# EDCPSU.net
KiCad netlist of a schematic drawn in EAGLE
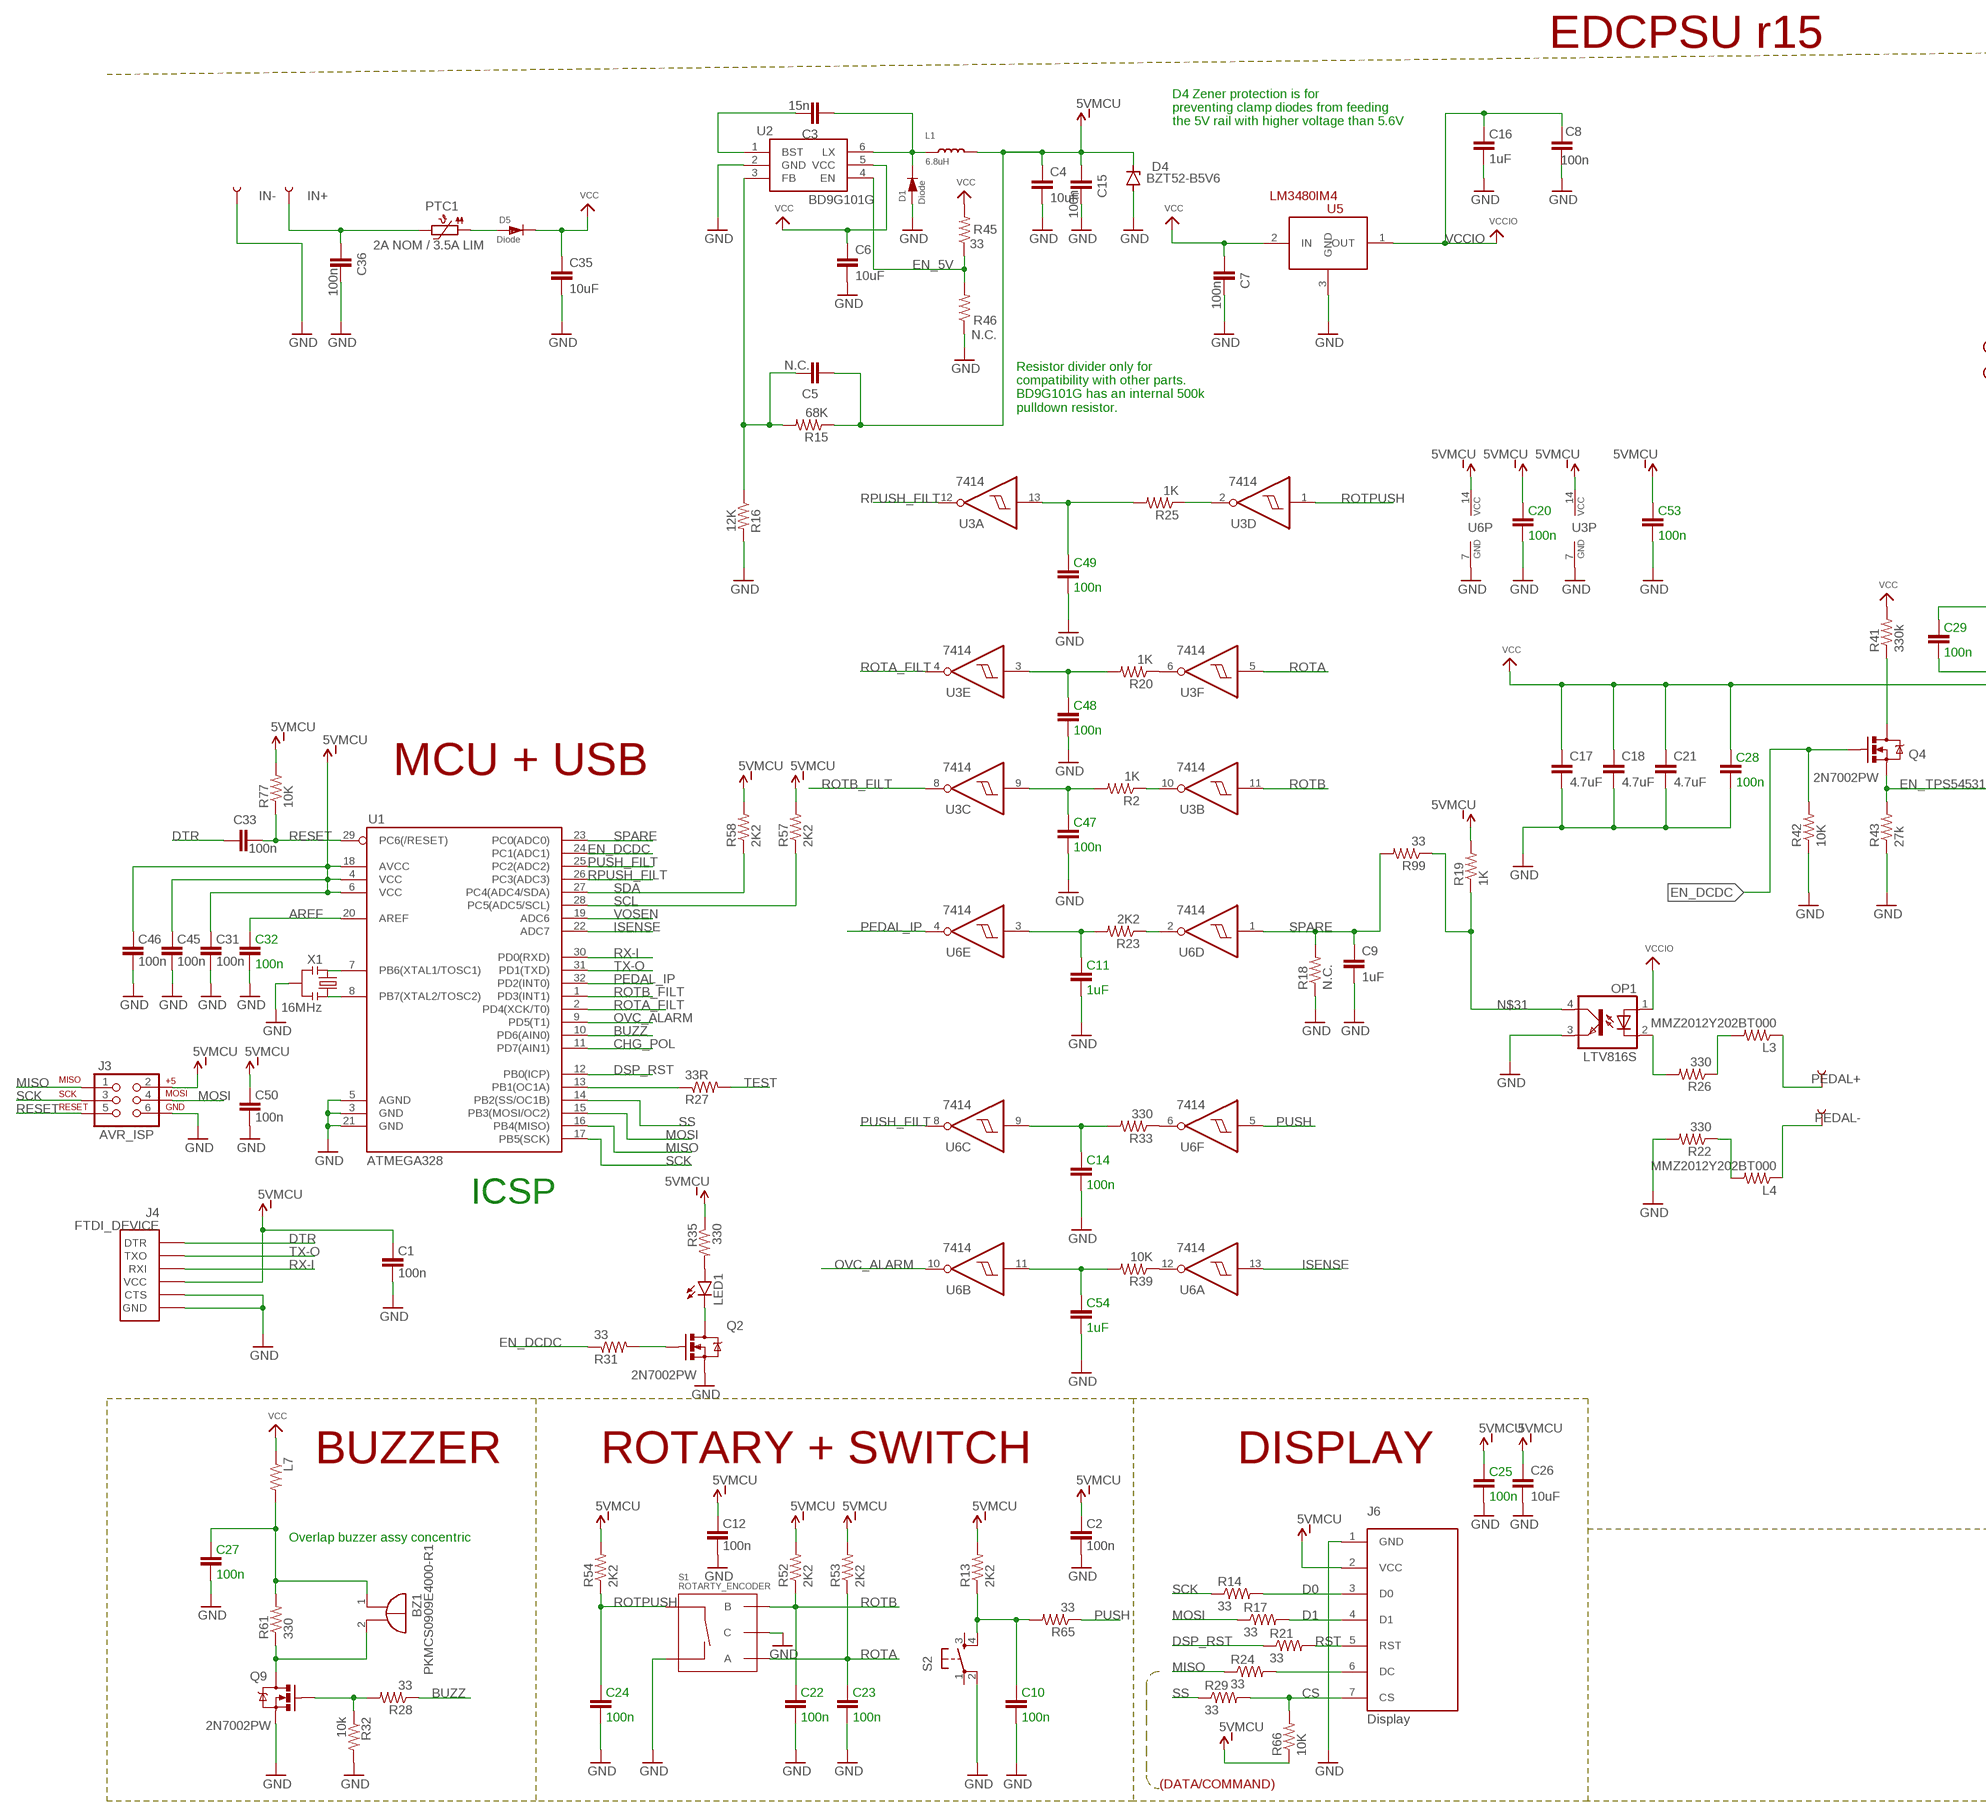
[diagram p0: schematic, sheet 1, part 1 of 2]
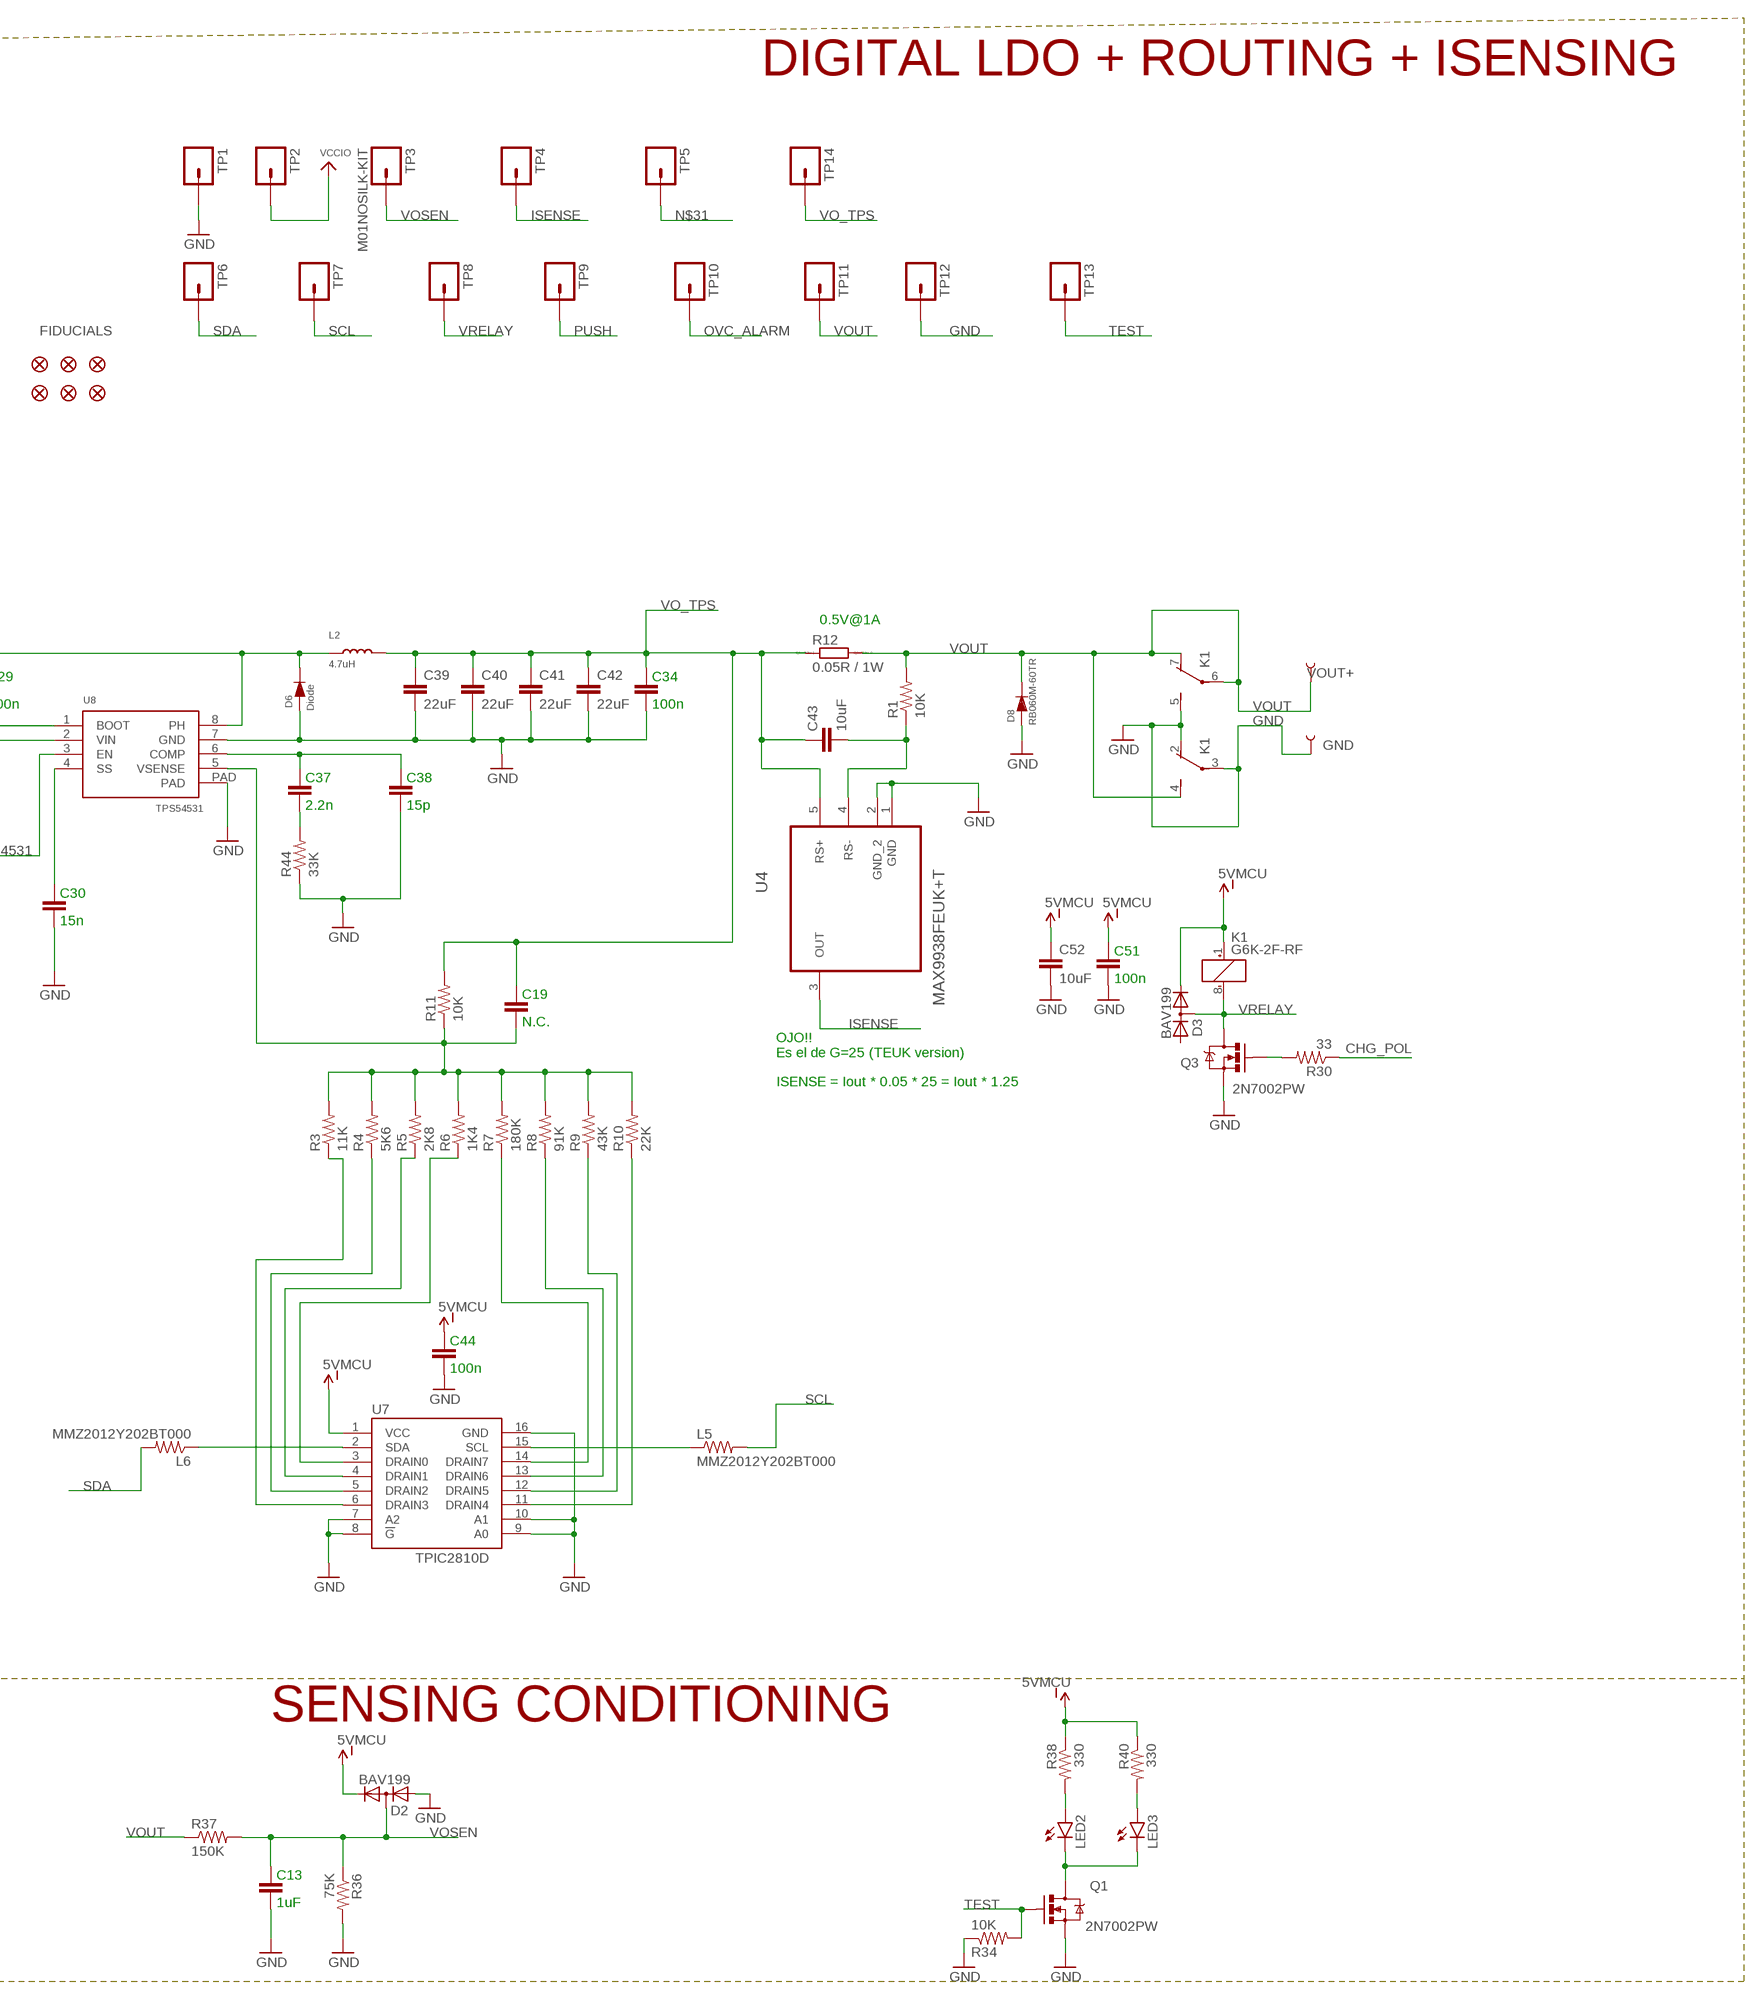
[diagram p1: schematic, sheet 1, part 2 of 2]

(export (version "E")
  (design (tool "Eeschema 10.0.6"))
  (components
    (comp (ref "BZ1")
      (value "PKMCS0909E4000-R1")
      (footprint "eagle-import:PKMCS0909")
      (libsource (lib "eagle-import") (part "PKMCS0909E4000-R1"))
    )
    (comp (ref "C1")
      (value "100n")
      (footprint "eagle-import:0805")
      (libsource (lib "eagle-import") (part "CAP0805"))
    )
    (comp (ref "C2")
      (value "100n")
      (footprint "eagle-import:0805")
      (libsource (lib "eagle-import") (part "CAP0805"))
    )
    (comp (ref "C3")
      (value "15n")
      (footprint "eagle-import:0805")
      (libsource (lib "eagle-import") (part "CAP0805"))
    )
    (comp (ref "C4")
      (value "10uF")
      (footprint "eagle-import:1206")
      (libsource (lib "eagle-import") (part "SparkFun-Passives_CAP1206"))
    )
    (comp (ref "C5")
      (value "N.C.")
      (footprint "eagle-import:0805")
      (libsource (lib "eagle-import") (part "CAP0805"))
    )
    (comp (ref "C6")
      (value "10uF")
      (footprint "eagle-import:1206")
      (libsource (lib "eagle-import") (part "SparkFun-Passives_CAP1206"))
    )
    (comp (ref "C7")
      (value "100n")
      (footprint "eagle-import:0805")
      (libsource (lib "eagle-import") (part "CAP0805"))
    )
    (comp (ref "C8")
      (value "100n")
      (footprint "eagle-import:0805")
      (libsource (lib "eagle-import") (part "CAP0805"))
    )
    (comp (ref "C9")
      (value "1uF")
      (footprint "eagle-import:1206")
      (libsource (lib "eagle-import") (part "SparkFun-Passives_CAP1206"))
    )
    (comp (ref "C10")
      (value "100n")
      (footprint "eagle-import:0805")
      (libsource (lib "eagle-import") (part "CAP0805"))
    )
    (comp (ref "C11")
      (value "1uF")
      (footprint "eagle-import:0805")
      (libsource (lib "eagle-import") (part "CAP0805"))
    )
    (comp (ref "C12")
      (value "100n")
      (footprint "eagle-import:0805")
      (libsource (lib "eagle-import") (part "CAP0805"))
    )
    (comp (ref "C13")
      (value "1uF")
      (footprint "eagle-import:0805")
      (libsource (lib "eagle-import") (part "CAP0805"))
    )
    (comp (ref "C14")
      (value "100n")
      (footprint "eagle-import:0805")
      (libsource (lib "eagle-import") (part "CAP0805"))
    )
    (comp (ref "C15")
      (value "100n")
      (footprint "eagle-import:0805")
      (libsource (lib "eagle-import") (part "CAP0805"))
    )
    (comp (ref "C16")
      (value "1uF")
      (footprint "eagle-import:0805")
      (libsource (lib "eagle-import") (part "CAP0805"))
    )
    (comp (ref "C17")
      (value "4.7uF")
      (footprint "eagle-import:1210")
      (libsource (lib "eagle-import") (part "SparkFun-Passives_CAP1210"))
    )
    (comp (ref "C18")
      (value "4.7uF")
      (footprint "eagle-import:1210")
      (libsource (lib "eagle-import") (part "SparkFun-Passives_CAP1210"))
    )
    (comp (ref "C19")
      (value "N.C.")
      (footprint "eagle-import:0805")
      (libsource (lib "eagle-import") (part "CAP0805"))
    )
    (comp (ref "C20")
      (value "100n")
      (footprint "eagle-import:0805")
      (libsource (lib "eagle-import") (part "CAP0805"))
    )
    (comp (ref "C21")
      (value "4.7uF")
      (footprint "eagle-import:1210")
      (libsource (lib "eagle-import") (part "SparkFun-Passives_CAP1210"))
    )
    (comp (ref "C22")
      (value "100n")
      (footprint "eagle-import:0805")
      (libsource (lib "eagle-import") (part "CAP0805"))
    )
    (comp (ref "C23")
      (value "100n")
      (footprint "eagle-import:0805")
      (libsource (lib "eagle-import") (part "CAP0805"))
    )
    (comp (ref "C24")
      (value "100n")
      (footprint "eagle-import:0805")
      (libsource (lib "eagle-import") (part "CAP0805"))
    )
    (comp (ref "C25")
      (value "100n")
      (footprint "eagle-import:0805")
      (libsource (lib "eagle-import") (part "CAP0805"))
    )
    (comp (ref "C26")
      (value "10uF")
      (footprint "eagle-import:1206")
      (libsource (lib "eagle-import") (part "SparkFun-Passives_CAP1206"))
    )
    (comp (ref "C27")
      (value "100n")
      (footprint "eagle-import:0805")
      (libsource (lib "eagle-import") (part "CAP0805"))
    )
    (comp (ref "C28")
      (value "100n")
      (footprint "eagle-import:0805")
      (libsource (lib "eagle-import") (part "CAP0805"))
    )
    (comp (ref "C29")
      (value "100n")
      (footprint "eagle-import:0805")
      (libsource (lib "eagle-import") (part "CAP0805"))
    )
    (comp (ref "C30")
      (value "15n")
      (footprint "eagle-import:0805")
      (libsource (lib "eagle-import") (part "CAP0805"))
    )
    (comp (ref "C31")
      (value "100n")
      (footprint "eagle-import:0805")
      (libsource (lib "eagle-import") (part "CAP0805"))
    )
    (comp (ref "C32")
      (value "100n")
      (footprint "eagle-import:0805")
      (libsource (lib "eagle-import") (part "CAP0805"))
    )
    (comp (ref "C33")
      (value "100n")
      (footprint "eagle-import:0805")
      (libsource (lib "eagle-import") (part "CAP0805"))
    )
    (comp (ref "C34")
      (value "100n")
      (footprint "eagle-import:0805")
      (libsource (lib "eagle-import") (part "CAP0805"))
    )
    (comp (ref "C35")
      (value "10uF")
      (footprint "eagle-import:1206")
      (libsource (lib "eagle-import") (part "SparkFun-Passives_CAP1206"))
    )
    (comp (ref "C36")
      (value "100n")
      (footprint "eagle-import:0805")
      (libsource (lib "eagle-import") (part "CAP0805"))
    )
    (comp (ref "C37")
      (value "2.2n")
      (footprint "eagle-import:0805")
      (libsource (lib "eagle-import") (part "CAP0805"))
    )
    (comp (ref "C38")
      (value "15p")
      (footprint "eagle-import:0805")
      (libsource (lib "eagle-import") (part "CAP0805"))
    )
    (comp (ref "C39")
      (value "22uF")
      (footprint "eagle-import:1210")
      (libsource (lib "eagle-import") (part "SparkFun-Passives_CAP1210"))
    )
    (comp (ref "C40")
      (value "22uF")
      (footprint "eagle-import:1210")
      (libsource (lib "eagle-import") (part "SparkFun-Passives_CAP1210"))
    )
    (comp (ref "C41")
      (value "22uF")
      (footprint "eagle-import:1210")
      (libsource (lib "eagle-import") (part "SparkFun-Passives_CAP1210"))
    )
    (comp (ref "C42")
      (value "22uF")
      (footprint "eagle-import:1210")
      (libsource (lib "eagle-import") (part "SparkFun-Passives_CAP1210"))
    )
    (comp (ref "C43")
      (value "10uF")
      (footprint "eagle-import:1206")
      (libsource (lib "eagle-import") (part "SparkFun-Passives_CAP1206"))
    )
    (comp (ref "C44")
      (value "100n")
      (footprint "eagle-import:0805")
      (libsource (lib "eagle-import") (part "CAP0805"))
    )
    (comp (ref "C45")
      (value "100n")
      (footprint "eagle-import:0805")
      (libsource (lib "eagle-import") (part "CAP0805"))
    )
    (comp (ref "C46")
      (value "100n")
      (footprint "eagle-import:0805")
      (libsource (lib "eagle-import") (part "CAP0805"))
    )
    (comp (ref "C47")
      (value "100n")
      (footprint "eagle-import:0805")
      (libsource (lib "eagle-import") (part "CAP0805"))
    )
    (comp (ref "C48")
      (value "100n")
      (footprint "eagle-import:0805")
      (libsource (lib "eagle-import") (part "CAP0805"))
    )
    (comp (ref "C49")
      (value "100n")
      (footprint "eagle-import:0805")
      (libsource (lib "eagle-import") (part "CAP0805"))
    )
    (comp (ref "C50")
      (value "100n")
      (footprint "eagle-import:0805")
      (libsource (lib "eagle-import") (part "CAP0805"))
    )
    (comp (ref "C51")
      (value "100n")
      (footprint "eagle-import:0805")
      (libsource (lib "eagle-import") (part "CAP0805"))
    )
    (comp (ref "C52")
      (value "10uF")
      (footprint "eagle-import:1206")
      (libsource (lib "eagle-import") (part "SparkFun-Passives_CAP1206"))
    )
    (comp (ref "C53")
      (value "100n")
      (footprint "eagle-import:0805")
      (libsource (lib "eagle-import") (part "CAP0805"))
    )
    (comp (ref "C54")
      (value "1uF")
      (footprint "eagle-import:0805")
      (libsource (lib "eagle-import") (part "CAP0805"))
    )
    (comp (ref "D1")
      (value "Diode")
      (footprint "eagle-import:SOD123")
      (libsource (lib "eagle-import") (part "DSOD123"))
    )
    (comp (ref "D2")
      (value "BAV199")
      (footprint "eagle-import:SOT23")
      (libsource (lib "eagle-import") (part "BAV199"))
    )
    (comp (ref "D3")
      (value "BAV199")
      (footprint "eagle-import:SOT23")
      (libsource (lib "eagle-import") (part "BAV199"))
    )
    (comp (ref "D4")
      (value "BZT52-B5V6")
      (footprint "eagle-import:SODFL3718X115")
      (libsource (lib "eagle-import") (part "ZENERDO-219-AB(SOD123F)_"))
    )
    (comp (ref "D5")
      (value "Diode")
      (footprint "eagle-import:DO-214AB")
      (libsource (lib "eagle-import") (part "DSMC"))
    )
    (comp (ref "D6")
      (value "Diode")
      (footprint "eagle-import:DO-214AB")
      (libsource (lib "eagle-import") (part "DSMC"))
    )
    (comp (ref "D8")
      (value "RB060M-60TR")
      (footprint "eagle-import:SMADIODE")
      (libsource (lib "eagle-import") (part "DSMA"))
    )
    (comp (ref "FID1")
      (value "FIDUCIAL1X2")
      (footprint "eagle-import:FIDUCIAL-1X2")
      (libsource (lib "eagle-import") (part "FIDUCIAL1X2"))
    )
    (comp (ref "FID2")
      (value "FIDUCIAL1X2")
      (footprint "eagle-import:FIDUCIAL-1X2")
      (libsource (lib "eagle-import") (part "FIDUCIAL1X2"))
    )
    (comp (ref "FID3")
      (value "FIDUCIAL1X2")
      (footprint "eagle-import:FIDUCIAL-1X2")
      (libsource (lib "eagle-import") (part "FIDUCIAL1X2"))
    )
    (comp (ref "FID4")
      (value "FIDUCIAL1X2")
      (footprint "eagle-import:FIDUCIAL-1X2")
      (libsource (lib "eagle-import") (part "FIDUCIAL1X2"))
    )
    (comp (ref "FID5")
      (value "FIDUCIAL1X2")
      (footprint "eagle-import:FIDUCIAL-1X2")
      (libsource (lib "eagle-import") (part "FIDUCIAL1X2"))
    )
    (comp (ref "FID6")
      (value "FIDUCIAL1X2")
      (footprint "eagle-import:FIDUCIAL-1X2")
      (libsource (lib "eagle-import") (part "FIDUCIAL1X2"))
    )
    (comp (ref "GND")
      (value "TEST-POINT3")
      (footprint "eagle-import:PAD.03X.03")
      (libsource (lib "eagle-import") (part "TEST-POINT3"))
    )
    (comp (ref "IN+")
      (value "TEST-POINT3")
      (footprint "eagle-import:PAD.03X.03")
      (libsource (lib "eagle-import") (part "TEST-POINT3"))
    )
    (comp (ref "IN-")
      (value "TEST-POINT3")
      (footprint "eagle-import:PAD.03X.03")
      (libsource (lib "eagle-import") (part "TEST-POINT3"))
    )
    (comp (ref "J3")
      (value "AVR_ISP")
      (footprint "eagle-import:2X3")
      (libsource (lib "eagle-import") (part "AVR_SPI_PRG_6PTH"))
    )
    (comp (ref "J4")
      (value "FTDI_DEVICE")
      (footprint "eagle-import:FTDI_DEVICE_SIDE")
      (libsource (lib "eagle-import") (part "FTDI_DEVICE"))
    )
    (comp (ref "J6")
      (value "Display")
      (footprint "eagle-import:OLED_LCD")
      (libsource (lib "eagle-import") (part "OLED_LCD"))
    )
    (comp (ref "K1")
      (value "G6K-2F-RF")
      (footprint "eagle-import:G6K-RF")
      (fields (field (name "MF") "OMRON COMPONENTS USA") (field (name "MPN") "G6K-2F-RF-DC12"))
      (libsource (lib "eagle-import") (part "G6K-2F-RF"))
    )
    (comp (ref "L1")
      (value "6.8uH")
      (footprint "eagle-import:NR4018T100M")
      (libsource (lib "eagle-import") (part "L4018"))
    )
    (comp (ref "L2")
      (value "4.7uH")
      (footprint "eagle-import:WE-LHMI")
      (libsource (lib "eagle-import") (part "L74437368047"))
    )
    (comp (ref "L3")
      (value "MMZ2012Y202BT000")
      (footprint "eagle-import:0805")
      (libsource (lib "eagle-import") (part "RESISTOR0805-RES"))
    )
    (comp (ref "L4")
      (value "MMZ2012Y202BT000")
      (footprint "eagle-import:0805")
      (libsource (lib "eagle-import") (part "RESISTOR0805-RES"))
    )
    (comp (ref "L5")
      (value "MMZ2012Y202BT000")
      (footprint "eagle-import:0805")
      (libsource (lib "eagle-import") (part "RESISTOR0805-RES"))
    )
    (comp (ref "L6")
      (value "MMZ2012Y202BT000")
      (footprint "eagle-import:0805")
      (libsource (lib "eagle-import") (part "RESISTOR0805-RES"))
    )
    (comp (ref "L7")
      (value "MMZ2012Y202BT000")
      (footprint "eagle-import:0805")
      (libsource (lib "eagle-import") (part "RESISTOR0805-RES"))
    )
    (comp (ref "LED1")
      (value "LED3MM")
      (footprint "eagle-import:LED3MM")
      (libsource (lib "eagle-import") (part "LED3MM"))
    )
    (comp (ref "LED2")
      (value "LED5MM")
      (footprint "eagle-import:LED5MM")
      (libsource (lib "eagle-import") (part "LED5MM"))
    )
    (comp (ref "LED3")
      (value "LED5MM")
      (footprint "eagle-import:LED5MM")
      (libsource (lib "eagle-import") (part "LED5MM"))
    )
    (comp (ref "OP1")
      (value "LTV816S")
      (footprint "eagle-import:SMD4")
      (libsource (lib "eagle-import") (part "LTV816S"))
    )
    (comp (ref "PEDAL+")
      (value "TEST-POINT3")
      (footprint "eagle-import:PAD.03X.03")
      (libsource (lib "eagle-import") (part "TEST-POINT3"))
    )
    (comp (ref "PEDAL-")
      (value "TEST-POINT3")
      (footprint "eagle-import:PAD.03X.03")
      (libsource (lib "eagle-import") (part "TEST-POINT3"))
    )
    (comp (ref "PTC1")
      (value "2A NOM / 3.5A LIM")
      (footprint "eagle-import:1812L")
      (libsource (lib "eagle-import") (part "PTC-"))
    )
    (comp (ref "Q1")
      (value "2N7002PW")
      (footprint "eagle-import:SOT323")
      (libsource (lib "eagle-import") (part "MOSFET-NCHANNEL2N7002PW"))
    )
    (comp (ref "Q2")
      (value "2N7002PW")
      (footprint "eagle-import:SOT323")
      (libsource (lib "eagle-import") (part "MOSFET-NCHANNEL2N7002PW"))
    )
    (comp (ref "Q3")
      (value "2N7002PW")
      (footprint "eagle-import:SOT323")
      (libsource (lib "eagle-import") (part "MOSFET-NCHANNEL2N7002PW"))
    )
    (comp (ref "Q4")
      (value "2N7002PW")
      (footprint "eagle-import:SOT323")
      (libsource (lib "eagle-import") (part "MOSFET-NCHANNEL2N7002PW"))
    )
    (comp (ref "Q9")
      (value "2N7002PW")
      (footprint "eagle-import:SOT323")
      (libsource (lib "eagle-import") (part "MOSFET-NCHANNEL2N7002PW"))
    )
    (comp (ref "R1")
      (value "10K")
      (footprint "eagle-import:0805")
      (libsource (lib "eagle-import") (part "RESISTOR0805-RES"))
    )
    (comp (ref "R2")
      (value "1K")
      (footprint "eagle-import:0805")
      (libsource (lib "eagle-import") (part "RESISTOR0805-RES"))
    )
    (comp (ref "R3")
      (value "11K")
      (footprint "eagle-import:0805")
      (libsource (lib "eagle-import") (part "RESISTOR0805-RES"))
    )
    (comp (ref "R4")
      (value "5K6")
      (footprint "eagle-import:0805")
      (libsource (lib "eagle-import") (part "RESISTOR0805-RES"))
    )
    (comp (ref "R5")
      (value "2K8")
      (footprint "eagle-import:0805")
      (libsource (lib "eagle-import") (part "RESISTOR0805-RES"))
    )
    (comp (ref "R6")
      (value "1K4")
      (footprint "eagle-import:0805")
      (libsource (lib "eagle-import") (part "RESISTOR0805-RES"))
    )
    (comp (ref "R7")
      (value "180K")
      (footprint "eagle-import:0805")
      (libsource (lib "eagle-import") (part "RESISTOR0805-RES"))
    )
    (comp (ref "R8")
      (value "91K")
      (footprint "eagle-import:0805")
      (libsource (lib "eagle-import") (part "RESISTOR0805-RES"))
    )
    (comp (ref "R9")
      (value "43K")
      (footprint "eagle-import:0805")
      (libsource (lib "eagle-import") (part "RESISTOR0805-RES"))
    )
    (comp (ref "R10")
      (value "22K")
      (footprint "eagle-import:0805")
      (libsource (lib "eagle-import") (part "RESISTOR0805-RES"))
    )
    (comp (ref "R11")
      (value "10K")
      (footprint "eagle-import:0805")
      (libsource (lib "eagle-import") (part "RESISTOR0805-RES"))
    )
    (comp (ref "R12")
      (value "0.05R / 1W")
      (footprint "eagle-import:R2512")
      (libsource (lib "eagle-import") (part "RR2512"))
    )
    (comp (ref "R13")
      (value "2K2")
      (footprint "eagle-import:0805")
      (libsource (lib "eagle-import") (part "RESISTOR0805-RES"))
    )
    (comp (ref "R14")
      (value "33")
      (footprint "eagle-import:0805")
      (libsource (lib "eagle-import") (part "RESISTOR0805-RES"))
    )
    (comp (ref "R15")
      (value "68K")
      (footprint "eagle-import:0805")
      (libsource (lib "eagle-import") (part "RESISTOR0805-RES"))
    )
    (comp (ref "R16")
      (value "12K")
      (footprint "eagle-import:0805")
      (libsource (lib "eagle-import") (part "RESISTOR0805-RES"))
    )
    (comp (ref "R17")
      (value "33")
      (footprint "eagle-import:0805")
      (libsource (lib "eagle-import") (part "RESISTOR0805-RES"))
    )
    (comp (ref "R18")
      (value "N.C.")
      (footprint "eagle-import:0805")
      (libsource (lib "eagle-import") (part "RESISTOR0805-RES"))
    )
    (comp (ref "R19")
      (value "1K")
      (footprint "eagle-import:0805")
      (libsource (lib "eagle-import") (part "RESISTOR0805-RES"))
    )
    (comp (ref "R20")
      (value "1K")
      (footprint "eagle-import:0805")
      (libsource (lib "eagle-import") (part "RESISTOR0805-RES"))
    )
    (comp (ref "R21")
      (value "33")
      (footprint "eagle-import:0805")
      (libsource (lib "eagle-import") (part "RESISTOR0805-RES"))
    )
    (comp (ref "R22")
      (value "330")
      (footprint "eagle-import:1206")
      (libsource (lib "eagle-import") (part "SparkFun-Passives_RESISTOR1206"))
    )
    (comp (ref "R23")
      (value "2K2")
      (footprint "eagle-import:0805")
      (libsource (lib "eagle-import") (part "RESISTOR0805-RES"))
    )
    (comp (ref "R24")
      (value "33")
      (footprint "eagle-import:0805")
      (libsource (lib "eagle-import") (part "RESISTOR0805-RES"))
    )
    (comp (ref "R25")
      (value "1K")
      (footprint "eagle-import:0805")
      (libsource (lib "eagle-import") (part "RESISTOR0805-RES"))
    )
    (comp (ref "R26")
      (value "330")
      (footprint "eagle-import:1206")
      (libsource (lib "eagle-import") (part "SparkFun-Passives_RESISTOR1206"))
    )
    (comp (ref "R27")
      (value "33R")
      (footprint "eagle-import:0805")
      (libsource (lib "eagle-import") (part "RESISTOR0805-RES"))
    )
    (comp (ref "R28")
      (value "33")
      (footprint "eagle-import:0805")
      (libsource (lib "eagle-import") (part "RESISTOR0805-RES"))
    )
    (comp (ref "R29")
      (value "33")
      (footprint "eagle-import:0805")
      (libsource (lib "eagle-import") (part "RESISTOR0805-RES"))
    )
    (comp (ref "R30")
      (value "33")
      (footprint "eagle-import:0805")
      (libsource (lib "eagle-import") (part "RESISTOR0805-RES"))
    )
    (comp (ref "R31")
      (value "33")
      (footprint "eagle-import:0805")
      (libsource (lib "eagle-import") (part "RESISTOR0805-RES"))
    )
    (comp (ref "R32")
      (value "10k")
      (footprint "eagle-import:0805")
      (libsource (lib "eagle-import") (part "RESISTOR0805-RES"))
    )
    (comp (ref "R33")
      (value "330")
      (footprint "eagle-import:0805")
      (libsource (lib "eagle-import") (part "RESISTOR0805-RES"))
    )
    (comp (ref "R34")
      (value "10K")
      (footprint "eagle-import:0805")
      (libsource (lib "eagle-import") (part "RESISTOR0805-RES"))
    )
    (comp (ref "R35")
      (value "330")
      (footprint "eagle-import:0805")
      (libsource (lib "eagle-import") (part "RESISTOR0805-RES"))
    )
    (comp (ref "R36")
      (value "75K")
      (footprint "eagle-import:0805")
      (libsource (lib "eagle-import") (part "RESISTOR0805-RES"))
    )
    (comp (ref "R37")
      (value "150K")
      (footprint "eagle-import:0805")
      (libsource (lib "eagle-import") (part "RESISTOR0805-RES"))
    )
    (comp (ref "R38")
      (value "330")
      (footprint "eagle-import:0805")
      (libsource (lib "eagle-import") (part "RESISTOR0805-RES"))
    )
    (comp (ref "R39")
      (value "10K")
      (footprint "eagle-import:0805")
      (libsource (lib "eagle-import") (part "RESISTOR0805-RES"))
    )
    (comp (ref "R40")
      (value "330")
      (footprint "eagle-import:0805")
      (libsource (lib "eagle-import") (part "RESISTOR0805-RES"))
    )
    (comp (ref "R41")
      (value "330k")
      (footprint "eagle-import:0805")
      (libsource (lib "eagle-import") (part "RESISTOR0805-RES"))
    )
    (comp (ref "R42")
      (value "10K")
      (footprint "eagle-import:0805")
      (libsource (lib "eagle-import") (part "RESISTOR0805-RES"))
    )
    (comp (ref "R43")
      (value "27k")
      (footprint "eagle-import:0805")
      (libsource (lib "eagle-import") (part "RESISTOR0805-RES"))
    )
    (comp (ref "R44")
      (value "33K")
      (footprint "eagle-import:0805")
      (libsource (lib "eagle-import") (part "RESISTOR0805-RES"))
    )
    (comp (ref "R45")
      (value "33")
      (footprint "eagle-import:0805")
      (libsource (lib "eagle-import") (part "RESISTOR0805-RES"))
    )
    (comp (ref "R46")
      (value "N.C.")
      (footprint "eagle-import:0805")
      (libsource (lib "eagle-import") (part "RESISTOR0805-RES"))
    )
    (comp (ref "R52")
      (value "2K2")
      (footprint "eagle-import:0805")
      (libsource (lib "eagle-import") (part "RESISTOR0805-RES"))
    )
    (comp (ref "R53")
      (value "2K2")
      (footprint "eagle-import:0805")
      (libsource (lib "eagle-import") (part "RESISTOR0805-RES"))
    )
    (comp (ref "R54")
      (value "2K2")
      (footprint "eagle-import:0805")
      (libsource (lib "eagle-import") (part "RESISTOR0805-RES"))
    )
    (comp (ref "R57")
      (value "2K2")
      (footprint "eagle-import:0805")
      (libsource (lib "eagle-import") (part "RESISTOR0805-RES"))
    )
    (comp (ref "R58")
      (value "2K2")
      (footprint "eagle-import:0805")
      (libsource (lib "eagle-import") (part "RESISTOR0805-RES"))
    )
    (comp (ref "R61")
      (value "330")
      (footprint "eagle-import:0805")
      (libsource (lib "eagle-import") (part "RESISTOR0805-RES"))
    )
    (comp (ref "R65")
      (value "33")
      (footprint "eagle-import:0805")
      (libsource (lib "eagle-import") (part "RESISTOR0805-RES"))
    )
    (comp (ref "R66")
      (value "10K")
      (footprint "eagle-import:0805")
      (libsource (lib "eagle-import") (part "RESISTOR0805-RES"))
    )
    (comp (ref "R77")
      (value "10K")
      (footprint "eagle-import:0805")
      (libsource (lib "eagle-import") (part "RESISTOR0805-RES"))
    )
    (comp (ref "R99")
      (value "33")
      (footprint "eagle-import:0805")
      (libsource (lib "eagle-import") (part "RESISTOR0805-RES"))
    )
    (comp (ref "S1")
      (value "ROTARTY_ENCODER")
      (footprint "eagle-import:ROTARY_ENC_PLAIN")
      (libsource (lib "eagle-import") (part "ROTARTY_ENCODER"))
    )
    (comp (ref "S2")
      (value "TAC_SWITCH_KSC931G-SMD")
      (footprint "eagle-import:TAC_SW_SMD_KSC931G")
      (libsource (lib "eagle-import") (part "TAC_SWITCH_KSC931G-SMD"))
    )
    (comp (ref "TP1")
      (value "M01POGOPIN_HOLE_LARGE")
      (footprint "eagle-import:1X01_POGOPIN_HOLE_LARGE")
      (libsource (lib "eagle-import") (part "M01POGOPIN_HOLE_LARGE"))
    )
    (comp (ref "TP2")
      (value "M01POGOPIN_HOLE_LARGE")
      (footprint "eagle-import:1X01_POGOPIN_HOLE_LARGE")
      (libsource (lib "eagle-import") (part "M01POGOPIN_HOLE_LARGE"))
    )
    (comp (ref "TP3")
      (value "M01NOSILK-KIT")
      (footprint "eagle-import:1X01NS-KIT")
      (libsource (lib "eagle-import") (part "M01NOSILK-KIT"))
    )
    (comp (ref "TP4")
      (value "M01POGOPIN_HOLE_LARGE")
      (footprint "eagle-import:1X01_POGOPIN_HOLE_LARGE")
      (libsource (lib "eagle-import") (part "M01POGOPIN_HOLE_LARGE"))
    )
    (comp (ref "TP5")
      (value "M01POGOPIN_HOLE_LARGE")
      (footprint "eagle-import:1X01_POGOPIN_HOLE_LARGE")
      (libsource (lib "eagle-import") (part "M01POGOPIN_HOLE_LARGE"))
    )
    (comp (ref "TP6")
      (value "M01POGOPIN_HOLE_LARGE")
      (footprint "eagle-import:1X01_POGOPIN_HOLE_LARGE")
      (libsource (lib "eagle-import") (part "M01POGOPIN_HOLE_LARGE"))
    )
    (comp (ref "TP7")
      (value "M01POGOPIN_HOLE_LARGE")
      (footprint "eagle-import:1X01_POGOPIN_HOLE_LARGE")
      (libsource (lib "eagle-import") (part "M01POGOPIN_HOLE_LARGE"))
    )
    (comp (ref "TP8")
      (value "M01POGOPIN_HOLE_LARGE")
      (footprint "eagle-import:1X01_POGOPIN_HOLE_LARGE")
      (libsource (lib "eagle-import") (part "M01POGOPIN_HOLE_LARGE"))
    )
    (comp (ref "TP9")
      (value "M01POGOPIN_HOLE_LARGE")
      (footprint "eagle-import:1X01_POGOPIN_HOLE_LARGE")
      (libsource (lib "eagle-import") (part "M01POGOPIN_HOLE_LARGE"))
    )
    (comp (ref "TP10")
      (value "M01POGOPIN_HOLE_LARGE")
      (footprint "eagle-import:1X01_POGOPIN_HOLE_LARGE")
      (libsource (lib "eagle-import") (part "M01POGOPIN_HOLE_LARGE"))
    )
    (comp (ref "TP11")
      (value "M01POGOPIN_HOLE_LARGE")
      (footprint "eagle-import:1X01_POGOPIN_HOLE_LARGE")
      (libsource (lib "eagle-import") (part "M01POGOPIN_HOLE_LARGE"))
    )
    (comp (ref "TP12")
      (value "M01POGOPIN_HOLE_LARGE")
      (footprint "eagle-import:1X01_POGOPIN_HOLE_LARGE")
      (libsource (lib "eagle-import") (part "M01POGOPIN_HOLE_LARGE"))
    )
    (comp (ref "TP13")
      (value "M01POGOPIN_HOLE_LARGE")
      (footprint "eagle-import:1X01_POGOPIN_HOLE_LARGE")
      (libsource (lib "eagle-import") (part "M01POGOPIN_HOLE_LARGE"))
    )
    (comp (ref "TP14")
      (value "M01POGOPIN_HOLE_LARGE")
      (footprint "eagle-import:1X01_POGOPIN_HOLE_LARGE")
      (libsource (lib "eagle-import") (part "M01POGOPIN_HOLE_LARGE"))
    )
    (comp (ref "U1")
      (value "ATMEGA328")
      (footprint "eagle-import:TQFP32-08")
      (libsource (lib "eagle-import") (part "ATMEGA168"))
    )
    (comp (ref "U2")
      (value "BD9G101G")
      (footprint "eagle-import:SSOP6")
      (libsource (lib "eagle-import") (part "BD9G101G"))
    )
    (comp (ref "U3")
      (value "7414")
      (footprint "eagle-import:TSSOP14")
      (libsource (lib "eagle-import") (part "7414"))
    )
    (comp (ref "U4")
      (value "MAX9938FEUK+T")
      (footprint "eagle-import:SOT95P280X145-5N")
      (libsource (lib "eagle-import") (part "MAX9938FEUK+T"))
    )
    (comp (ref "U5")
      (value "LM3480IM4")
      (footprint "eagle-import:SOT23-3")
      (libsource (lib "eagle-import") (part "LM3480IM4"))
    )
    (comp (ref "U6")
      (value "7414")
      (footprint "eagle-import:TSSOP14")
      (libsource (lib "eagle-import") (part "7414"))
    )
    (comp (ref "U7")
      (value "TPIC2810D")
      (footprint "eagle-import:SO16")
      (libsource (lib "eagle-import") (part "TPIC2810D"))
    )
    (comp (ref "U8")
      (value "TPS54531")
      (footprint "eagle-import:SOIC8")
      (libsource (lib "eagle-import") (part "TPS5431DDAR"))
    )
    (comp (ref "VOUT+")
      (value "TEST-POINT3")
      (footprint "eagle-import:PAD.03X.03")
      (libsource (lib "eagle-import") (part "TEST-POINT3"))
    )
    (comp (ref "X1")
      (value "16MHz")
      (footprint "eagle-import:RESONATOR-SMD")
      (libsource (lib "eagle-import") (part "RESONATORSMD"))
    )
  )
  (nets
    (net (code "1") (name "/AREF") (class "Default")
      (node (ref "C32") (pin "2") (pinfunction "2_2") (pintype "passive"))
      (node (ref "U1") (pin "20") (pinfunction "AREF_20") (pintype "bidirectional"))
    )
    (net (code "2") (name "/BUZZ") (class "Default")
      (node (ref "R28") (pin "1") (pinfunction "1_1") (pintype "passive"))
      (node (ref "U1") (pin "10") (pinfunction "PD6(AIN0)_10") (pintype "bidirectional"))
    )
    (net (code "3") (name "/CHG_POL") (class "Default")
      (node (ref "R30") (pin "1") (pinfunction "1_1") (pintype "passive"))
      (node (ref "U1") (pin "11") (pinfunction "PD7(AIN1)_11") (pintype "bidirectional"))
    )
    (net (code "4") (name "/CS") (class "Default")
      (node (ref "J6") (pin "7") (pinfunction "CS_7") (pintype "bidirectional"))
      (node (ref "R29") (pin "2") (pinfunction "2_2") (pintype "passive"))
      (node (ref "R66") (pin "2") (pinfunction "2_2") (pintype "passive"))
    )
    (net (code "5") (name "/D0") (class "Default")
      (node (ref "J6") (pin "3") (pinfunction "D0_3") (pintype "bidirectional"))
      (node (ref "R14") (pin "2") (pinfunction "2_2") (pintype "passive"))
    )
    (net (code "6") (name "/D1") (class "Default")
      (node (ref "J6") (pin "4") (pinfunction "D1_4") (pintype "bidirectional"))
      (node (ref "R17") (pin "2") (pinfunction "2_2") (pintype "passive"))
    )
    (net (code "7") (name "/DSP_RST") (class "Default")
      (node (ref "R21") (pin "1") (pinfunction "1_1") (pintype "passive"))
      (node (ref "U1") (pin "12") (pinfunction "PB0(ICP)_12") (pintype "bidirectional"))
    )
    (net (code "8") (name "/DTR") (class "Default")
      (node (ref "C33") (pin "2") (pinfunction "2_2") (pintype "passive"))
      (node (ref "J4") (pin "P$1") (pinfunction "DTR_P$1") (pintype "bidirectional"))
    )
    (net (code "9") (name "/EN_5V") (class "Default")
      (node (ref "R45") (pin "1") (pinfunction "1_1") (pintype "passive"))
      (node (ref "R46") (pin "2") (pinfunction "2_2") (pintype "passive"))
      (node (ref "U2") (pin "4") (pinfunction "EN_4") (pintype "bidirectional"))
    )
    (net (code "10") (name "/EN_TPS54531") (class "Default")
      (node (ref "Q4") (pin "2") (pinfunction "S_2") (pintype "passive"))
      (node (ref "R43") (pin "2") (pinfunction "2_2") (pintype "passive"))
      (node (ref "U8") (pin "3") (pinfunction "EN_3") (pintype "bidirectional"))
    )
    (net (code "11") (name "/ISENSE") (class "Default")
      (node (ref "TP4") (pin "1") (pinfunction "1_1") (pintype "passive"))
      (node (ref "U1") (pin "22") (pinfunction "ADC7_22") (pintype "bidirectional"))
      (node (ref "U4") (pin "3") (pinfunction "OUT_3") (pintype "output"))
      (node (ref "U6") (pin "13") (pinfunction "I_13") (pintype "input"))
    )
    (net (code "12") (name "/MISO") (class "Default")
      (node (ref "J3") (pin "1") (pinfunction "1_1") (pintype "passive"))
      (node (ref "R24") (pin "1") (pinfunction "1_1") (pintype "passive"))
      (node (ref "U1") (pin "16") (pinfunction "PB4(MISO)_16") (pintype "bidirectional"))
    )
    (net (code "13") (name "/MOSI") (class "Default")
      (node (ref "J3") (pin "4") (pinfunction "4_4") (pintype "passive"))
      (node (ref "R17") (pin "1") (pinfunction "1_1") (pintype "passive"))
      (node (ref "U1") (pin "15") (pinfunction "PB3(MOSI/OC2)_15") (pintype "bidirectional"))
    )
    (net (code "14") (name "/N$31") (class "Default")
      (node (ref "OP1") (pin "4") (pinfunction "COL_4") (pintype "passive"))
      (node (ref "R19") (pin "1") (pinfunction "1_1") (pintype "passive"))
      (node (ref "R99") (pin "1") (pinfunction "1_1") (pintype "passive"))
      (node (ref "TP5") (pin "1") (pinfunction "1_1") (pintype "passive"))
    )
    (net (code "15") (name "/OVC_ALARM") (class "Default")
      (node (ref "TP10") (pin "1") (pinfunction "1_1") (pintype "passive"))
      (node (ref "U1") (pin "9") (pinfunction "PD5(T1)_9") (pintype "bidirectional"))
      (node (ref "U6") (pin "10") (pinfunction "O_10") (pintype "output"))
    )
    (net (code "16") (name "/PEDAL_IP") (class "Default")
      (node (ref "U1") (pin "32") (pinfunction "PD2(INT0)_32") (pintype "bidirectional"))
      (node (ref "U6") (pin "4") (pinfunction "O_4") (pintype "output"))
    )
    (net (code "17") (name "/PUSH") (class "Default")
      (node (ref "R65") (pin "1") (pinfunction "1_1") (pintype "passive"))
      (node (ref "TP9") (pin "1") (pinfunction "1_1") (pintype "passive"))
      (node (ref "U6") (pin "5") (pinfunction "I_5") (pintype "input"))
    )
    (net (code "18") (name "/PUSH_FILT") (class "Default")
      (node (ref "U1") (pin "25") (pinfunction "PC2(ADC2)_25") (pintype "bidirectional"))
      (node (ref "U6") (pin "8") (pinfunction "O_8") (pintype "output"))
    )
    (net (code "19") (name "/RESET") (class "Default")
      (node (ref "C33") (pin "1") (pinfunction "1_1") (pintype "passive"))
      (node (ref "J3") (pin "5") (pinfunction "5_5") (pintype "passive"))
      (node (ref "R77") (pin "1") (pinfunction "1_1") (pintype "passive"))
      (node (ref "U1") (pin "29") (pinfunction "PC6(/RESET)_29") (pintype "bidirectional"))
    )
    (net (code "20") (name "/ROTA") (class "Default")
      (node (ref "C23") (pin "2") (pinfunction "2_2") (pintype "passive"))
      (node (ref "R53") (pin "1") (pinfunction "1_1") (pintype "passive"))
      (node (ref "S1") (pin "A") (pinfunction "A_A") (pintype "bidirectional"))
      (node (ref "U3") (pin "5") (pinfunction "I_5") (pintype "input"))
    )
    (net (code "21") (name "/ROTA_FILT") (class "Default")
      (node (ref "U1") (pin "2") (pinfunction "PD4(XCK/T0)_2") (pintype "bidirectional"))
      (node (ref "U3") (pin "4") (pinfunction "O_4") (pintype "output"))
    )
    (net (code "22") (name "/ROTB") (class "Default")
      (node (ref "C22") (pin "2") (pinfunction "2_2") (pintype "passive"))
      (node (ref "R52") (pin "1") (pinfunction "1_1") (pintype "passive"))
      (node (ref "S1") (pin "B") (pinfunction "B_B") (pintype "bidirectional"))
      (node (ref "U3") (pin "11") (pinfunction "I_11") (pintype "input"))
    )
    (net (code "23") (name "/ROTB_FILT") (class "Default")
      (node (ref "U1") (pin "1") (pinfunction "PD3(INT1)_1") (pintype "bidirectional"))
      (node (ref "U3") (pin "8") (pinfunction "O_8") (pintype "output"))
    )
    (net (code "24") (name "/ROTPUSH") (class "Default")
      (node (ref "C24") (pin "2") (pinfunction "2_2") (pintype "passive"))
      (node (ref "R54") (pin "1") (pinfunction "1_1") (pintype "passive"))
      (node (ref "S1") (pin "SW+") (pinfunction "SW+_SW+") (pintype "bidirectional"))
      (node (ref "U3") (pin "1") (pinfunction "I_1") (pintype "input"))
    )
    (net (code "25") (name "/RPUSH_FILT") (class "Default")
      (node (ref "U1") (pin "26") (pinfunction "PC3(ADC3)_26") (pintype "bidirectional"))
      (node (ref "U3") (pin "12") (pinfunction "O_12") (pintype "output"))
    )
    (net (code "26") (name "/RST") (class "Default")
      (node (ref "J6") (pin "5") (pinfunction "RST_5") (pintype "bidirectional"))
      (node (ref "R21") (pin "2") (pinfunction "2_2") (pintype "passive"))
    )
    (net (code "27") (name "/RX-I") (class "Default")
      (node (ref "J4") (pin "P$3") (pinfunction "RXI_P$3") (pintype "bidirectional"))
      (node (ref "U1") (pin "30") (pinfunction "PD0(RXD)_30") (pintype "bidirectional"))
    )
    (net (code "28") (name "/SCK") (class "Default")
      (node (ref "J3") (pin "3") (pinfunction "3_3") (pintype "passive"))
      (node (ref "R14") (pin "1") (pinfunction "1_1") (pintype "passive"))
      (node (ref "U1") (pin "17") (pinfunction "PB5(SCK)_17") (pintype "bidirectional"))
    )
    (net (code "29") (name "/SCL") (class "Default")
      (node (ref "L5") (pin "2") (pinfunction "2_2") (pintype "passive"))
      (node (ref "R57") (pin "1") (pinfunction "1_1") (pintype "passive"))
      (node (ref "TP7") (pin "1") (pinfunction "1_1") (pintype "passive"))
      (node (ref "U1") (pin "28") (pinfunction "PC5(ADC5/SCL)_28") (pintype "bidirectional"))
    )
    (net (code "30") (name "/SDA") (class "Default")
      (node (ref "L6") (pin "2") (pinfunction "2_2") (pintype "passive"))
      (node (ref "R58") (pin "1") (pinfunction "1_1") (pintype "passive"))
      (node (ref "TP6") (pin "1") (pinfunction "1_1") (pintype "passive"))
      (node (ref "U1") (pin "27") (pinfunction "PC4(ADC4/SDA)_27") (pintype "bidirectional"))
    )
    (net (code "31") (name "/SPARE") (class "Default")
      (node (ref "C9") (pin "1") (pinfunction "1_1") (pintype "passive"))
      (node (ref "R18") (pin "2") (pinfunction "2_2") (pintype "passive"))
      (node (ref "R99") (pin "2") (pinfunction "2_2") (pintype "passive"))
      (node (ref "U1") (pin "23") (pinfunction "PC0(ADC0)_23") (pintype "bidirectional"))
      (node (ref "U6") (pin "1") (pinfunction "I_1") (pintype "input"))
    )
    (net (code "32") (name "/SS") (class "Default")
      (node (ref "R29") (pin "1") (pinfunction "1_1") (pintype "passive"))
      (node (ref "U1") (pin "14") (pinfunction "PB2(SS/OC1B)_14") (pintype "bidirectional"))
    )
    (net (code "33") (name "/TEST") (class "Default")
      (node (ref "Q1") (pin "1") (pinfunction "G_1") (pintype "passive"))
      (node (ref "R27") (pin "2") (pinfunction "2_2") (pintype "passive"))
      (node (ref "R34") (pin "2") (pinfunction "2_2") (pintype "passive"))
      (node (ref "TP13") (pin "1") (pinfunction "1_1") (pintype "passive"))
    )
    (net (code "34") (name "/TX-O") (class "Default")
      (node (ref "J4") (pin "P$2") (pinfunction "TXO_P$2") (pintype "bidirectional"))
      (node (ref "U1") (pin "31") (pinfunction "PD1(TXD)_31") (pintype "bidirectional"))
    )
    (net (code "35") (name "/VOSEN") (class "Default")
      (node (ref "C13") (pin "2") (pinfunction "2_2") (pintype "passive"))
      (node (ref "D2") (pin "3") (pinfunction "AC_3") (pintype "passive"))
      (node (ref "R36") (pin "1") (pinfunction "1_1") (pintype "passive"))
      (node (ref "R37") (pin "2") (pinfunction "2_2") (pintype "passive"))
      (node (ref "TP3") (pin "1") (pinfunction "1_1") (pintype "passive"))
      (node (ref "U1") (pin "19") (pinfunction "ADC6_19") (pintype "bidirectional"))
    )
    (net (code "36") (name "/VOUT") (class "Default")
      (node (ref "D8") (pin "C") (pinfunction "K_C") (pintype "bidirectional"))
      (node (ref "K1") (pin "4") (pinfunction "S_4") (pintype "passive"))
      (node (ref "K1") (pin "6") (pinfunction "P_6") (pintype "passive"))
      (node (ref "K1") (pin "7") (pinfunction "O_7") (pintype "passive"))
      (node (ref "R1") (pin "2") (pinfunction "2_2") (pintype "passive"))
      (node (ref "R12") (pin "2") (pinfunction "2_2") (pintype "passive"))
      (node (ref "R37") (pin "1") (pinfunction "1_1") (pintype "passive"))
      (node (ref "TP11") (pin "1") (pinfunction "1_1") (pintype "passive"))
      (node (ref "VOUT+") (pin "P$1") (pinfunction "1_P$1") (pintype "bidirectional"))
    )
    (net (code "37") (name "/VO_TPS") (class "Default")
      (node (ref "C19") (pin "2") (pinfunction "2_2") (pintype "passive"))
      (node (ref "C34") (pin "2") (pinfunction "2_2") (pintype "passive"))
      (node (ref "C39") (pin "1") (pinfunction "1_1") (pintype "passive"))
      (node (ref "C40") (pin "1") (pinfunction "1_1") (pintype "passive"))
      (node (ref "C41") (pin "1") (pinfunction "1_1") (pintype "passive"))
      (node (ref "C42") (pin "1") (pinfunction "1_1") (pintype "passive"))
      (node (ref "C43") (pin "1") (pinfunction "1_1") (pintype "passive"))
      (node (ref "L2") (pin "2") (pinfunction "2_2") (pintype "passive"))
      (node (ref "R11") (pin "2") (pinfunction "2_2") (pintype "passive"))
      (node (ref "R12") (pin "1") (pinfunction "1_1") (pintype "passive"))
      (node (ref "TP14") (pin "1") (pinfunction "1_1") (pintype "passive"))
      (node (ref "U4") (pin "5") (pinfunction "RS+_5") (pintype "power_in"))
    )
    (net (code "38") (name "/VRELAY") (class "Default")
      (node (ref "D3") (pin "3") (pinfunction "AC_3") (pintype "passive"))
      (node (ref "K1") (pin "8") (pinfunction "-_8") (pintype "passive"))
      (node (ref "Q3") (pin "3") (pinfunction "D_3") (pintype "passive"))
      (node (ref "TP8") (pin "1") (pinfunction "1_1") (pintype "passive"))
    )
    (net (code "39") (name "5VMCU") (class "Default")
      (node (ref "C1") (pin "2") (pinfunction "2_2") (pintype "passive"))
      (node (ref "C12") (pin "2") (pinfunction "2_2") (pintype "passive"))
      (node (ref "C15") (pin "2") (pinfunction "2_2") (pintype "passive"))
      (node (ref "C2") (pin "2") (pinfunction "2_2") (pintype "passive"))
      (node (ref "C20") (pin "2") (pinfunction "2_2") (pintype "passive"))
      (node (ref "C25") (pin "2") (pinfunction "2_2") (pintype "passive"))
      (node (ref "C26") (pin "1") (pinfunction "1_1") (pintype "passive"))
      (node (ref "C31") (pin "2") (pinfunction "2_2") (pintype "passive"))
      (node (ref "C4") (pin "1") (pinfunction "1_1") (pintype "passive"))
      (node (ref "C44") (pin "2") (pinfunction "2_2") (pintype "passive"))
      (node (ref "C45") (pin "2") (pinfunction "2_2") (pintype "passive"))
      (node (ref "C46") (pin "2") (pinfunction "2_2") (pintype "passive"))
      (node (ref "C5") (pin "2") (pinfunction "2_2") (pintype "passive"))
      (node (ref "C50") (pin "2") (pinfunction "2_2") (pintype "passive"))
      (node (ref "C51") (pin "2") (pinfunction "2_2") (pintype "passive"))
      (node (ref "C52") (pin "1") (pinfunction "1_1") (pintype "passive"))
      (node (ref "C53") (pin "2") (pinfunction "2_2") (pintype "passive"))
      (node (ref "D2") (pin "2") (pinfunction "C_2") (pintype "passive"))
      (node (ref "D3") (pin "2") (pinfunction "C_2") (pintype "passive"))
      (node (ref "D4") (pin "2") (pinfunction "C_2") (pintype "passive"))
      (node (ref "J3") (pin "2") (pinfunction "2_2") (pintype "passive"))
      (node (ref "J4") (pin "P$4") (pinfunction "VCC_P$4") (pintype "bidirectional"))
      (node (ref "J6") (pin "2") (pinfunction "VCC_2") (pintype "bidirectional"))
      (node (ref "K1") (pin "1") (pinfunction "+_1") (pintype "passive"))
      (node (ref "L1") (pin "2") (pinfunction "2_2") (pintype "passive"))
      (node (ref "R13") (pin "2") (pinfunction "2_2") (pintype "passive"))
      (node (ref "R15") (pin "1") (pinfunction "1_1") (pintype "passive"))
      (node (ref "R19") (pin "2") (pinfunction "2_2") (pintype "passive"))
      (node (ref "R35") (pin "1") (pinfunction "1_1") (pintype "passive"))
      (node (ref "R38") (pin "1") (pinfunction "1_1") (pintype "passive"))
      (node (ref "R40") (pin "1") (pinfunction "1_1") (pintype "passive"))
      (node (ref "R52") (pin "2") (pinfunction "2_2") (pintype "passive"))
      (node (ref "R53") (pin "2") (pinfunction "2_2") (pintype "passive"))
      (node (ref "R54") (pin "2") (pinfunction "2_2") (pintype "passive"))
      (node (ref "R57") (pin "2") (pinfunction "2_2") (pintype "passive"))
      (node (ref "R58") (pin "2") (pinfunction "2_2") (pintype "passive"))
      (node (ref "R66") (pin "1") (pinfunction "1_1") (pintype "passive"))
      (node (ref "R77") (pin "2") (pinfunction "2_2") (pintype "passive"))
      (node (ref "U1") (pin "18") (pinfunction "AVCC_18") (pintype "bidirectional"))
      (node (ref "U1") (pin "4") (pinfunction "VCC_4") (pintype "bidirectional"))
      (node (ref "U1") (pin "6") (pinfunction "VCC_6") (pintype "bidirectional"))
      (node (ref "U3") (pin "14") (pinfunction "VCC_14") (pintype "power_in"))
      (node (ref "U6") (pin "14") (pinfunction "VCC_14") (pintype "power_in"))
      (node (ref "U7") (pin "1") (pinfunction "VCC_1") (pintype "bidirectional"))
    )
    (net (code "40") (name "EN_DCDC") (class "Default")
      (node (ref "Q4") (pin "1") (pinfunction "G_1") (pintype "passive"))
      (node (ref "R31") (pin "1") (pinfunction "1_1") (pintype "passive"))
      (node (ref "R42") (pin "2") (pinfunction "2_2") (pintype "passive"))
      (node (ref "U1") (pin "24") (pinfunction "PC1(ADC1)_24") (pintype "bidirectional"))
    )
    (net (code "41") (name "GND") (class "Default")
      (node (ref "C1") (pin "1") (pinfunction "1_1") (pintype "passive"))
      (node (ref "C10") (pin "1") (pinfunction "1_1") (pintype "passive"))
      (node (ref "C11") (pin "1") (pinfunction "1_1") (pintype "passive"))
      (node (ref "C12") (pin "1") (pinfunction "1_1") (pintype "passive"))
      (node (ref "C13") (pin "1") (pinfunction "1_1") (pintype "passive"))
      (node (ref "C14") (pin "1") (pinfunction "1_1") (pintype "passive"))
      (node (ref "C15") (pin "1") (pinfunction "1_1") (pintype "passive"))
      (node (ref "C16") (pin "1") (pinfunction "1_1") (pintype "passive"))
      (node (ref "C17") (pin "2") (pinfunction "2_2") (pintype "passive"))
      (node (ref "C18") (pin "2") (pinfunction "2_2") (pintype "passive"))
      (node (ref "C2") (pin "1") (pinfunction "1_1") (pintype "passive"))
      (node (ref "C20") (pin "1") (pinfunction "1_1") (pintype "passive"))
      (node (ref "C21") (pin "2") (pinfunction "2_2") (pintype "passive"))
      (node (ref "C22") (pin "1") (pinfunction "1_1") (pintype "passive"))
      (node (ref "C23") (pin "1") (pinfunction "1_1") (pintype "passive"))
      (node (ref "C24") (pin "1") (pinfunction "1_1") (pintype "passive"))
      (node (ref "C25") (pin "1") (pinfunction "1_1") (pintype "passive"))
      (node (ref "C26") (pin "2") (pinfunction "2_2") (pintype "passive"))
      (node (ref "C27") (pin "1") (pinfunction "1_1") (pintype "passive"))
      (node (ref "C28") (pin "1") (pinfunction "1_1") (pintype "passive"))
      (node (ref "C30") (pin "1") (pinfunction "1_1") (pintype "passive"))
      (node (ref "C31") (pin "1") (pinfunction "1_1") (pintype "passive"))
      (node (ref "C32") (pin "1") (pinfunction "1_1") (pintype "passive"))
      (node (ref "C34") (pin "1") (pinfunction "1_1") (pintype "passive"))
      (node (ref "C35") (pin "2") (pinfunction "2_2") (pintype "passive"))
      (node (ref "C36") (pin "1") (pinfunction "1_1") (pintype "passive"))
      (node (ref "C38") (pin "1") (pinfunction "1_1") (pintype "passive"))
      (node (ref "C39") (pin "2") (pinfunction "2_2") (pintype "passive"))
      (node (ref "C4") (pin "2") (pinfunction "2_2") (pintype "passive"))
      (node (ref "C40") (pin "2") (pinfunction "2_2") (pintype "passive"))
      (node (ref "C41") (pin "2") (pinfunction "2_2") (pintype "passive"))
      (node (ref "C42") (pin "2") (pinfunction "2_2") (pintype "passive"))
      (node (ref "C44") (pin "1") (pinfunction "1_1") (pintype "passive"))
      (node (ref "C45") (pin "1") (pinfunction "1_1") (pintype "passive"))
      (node (ref "C46") (pin "1") (pinfunction "1_1") (pintype "passive"))
      (node (ref "C47") (pin "1") (pinfunction "1_1") (pintype "passive"))
      (node (ref "C48") (pin "1") (pinfunction "1_1") (pintype "passive"))
      (node (ref "C49") (pin "1") (pinfunction "1_1") (pintype "passive"))
      (node (ref "C50") (pin "1") (pinfunction "1_1") (pintype "passive"))
      (node (ref "C51") (pin "1") (pinfunction "1_1") (pintype "passive"))
      (node (ref "C52") (pin "2") (pinfunction "2_2") (pintype "passive"))
      (node (ref "C53") (pin "1") (pinfunction "1_1") (pintype "passive"))
      (node (ref "C54") (pin "1") (pinfunction "1_1") (pintype "passive"))
      (node (ref "C6") (pin "2") (pinfunction "2_2") (pintype "passive"))
      (node (ref "C7") (pin "1") (pinfunction "1_1") (pintype "passive"))
      (node (ref "C8") (pin "1") (pinfunction "1_1") (pintype "passive"))
      (node (ref "C9") (pin "2") (pinfunction "2_2") (pintype "passive"))
      (node (ref "D1") (pin "+") (pinfunction "A_+") (pintype "bidirectional"))
      (node (ref "D2") (pin "1") (pinfunction "A_1") (pintype "passive"))
      (node (ref "D4") (pin "1") (pinfunction "A_1") (pintype "passive"))
      (node (ref "D6") (pin "1") (pinfunction "A_1") (pintype "bidirectional"))
      (node (ref "D8") (pin "A") (pinfunction "A_A") (pintype "bidirectional"))
      (node (ref "GND") (pin "P$1") (pinfunction "1_P$1") (pintype "bidirectional"))
      (node (ref "IN-") (pin "P$1") (pinfunction "1_P$1") (pintype "bidirectional"))
      (node (ref "J3") (pin "6") (pinfunction "6_6") (pintype "passive"))
      (node (ref "J4") (pin "P$5") (pinfunction "CTS_P$5") (pintype "bidirectional"))
      (node (ref "J4") (pin "P$6") (pinfunction "GND_P$6") (pintype "bidirectional"))
      (node (ref "J6") (pin "1") (pinfunction "GND_1") (pintype "bidirectional"))
      (node (ref "K1") (pin "2") (pinfunction "O_2") (pintype "passive"))
      (node (ref "K1") (pin "3") (pinfunction "P_3") (pintype "passive"))
      (node (ref "K1") (pin "5") (pinfunction "S_5") (pintype "passive"))
      (node (ref "OP1") (pin "3") (pinfunction "EMIT_3") (pintype "passive"))
      (node (ref "Q1") (pin "2") (pinfunction "S_2") (pintype "passive"))
      (node (ref "Q2") (pin "2") (pinfunction "S_2") (pintype "passive"))
      (node (ref "Q3") (pin "2") (pinfunction "S_2") (pintype "passive"))
      (node (ref "Q9") (pin "2") (pinfunction "S_2") (pintype "passive"))
      (node (ref "R16") (pin "2") (pinfunction "2_2") (pintype "passive"))
      (node (ref "R18") (pin "1") (pinfunction "1_1") (pintype "passive"))
      (node (ref "R22") (pin "2") (pinfunction "2_2") (pintype "passive"))
      (node (ref "R32") (pin "2") (pinfunction "2_2") (pintype "passive"))
      (node (ref "R34") (pin "1") (pinfunction "1_1") (pintype "passive"))
      (node (ref "R36") (pin "2") (pinfunction "2_2") (pintype "passive"))
      (node (ref "R42") (pin "1") (pinfunction "1_1") (pintype "passive"))
      (node (ref "R43") (pin "1") (pinfunction "1_1") (pintype "passive"))
      (node (ref "R44") (pin "1") (pinfunction "1_1") (pintype "passive"))
      (node (ref "R46") (pin "1") (pinfunction "1_1") (pintype "passive"))
      (node (ref "S1") (pin "C") (pinfunction "C_C") (pintype "bidirectional"))
      (node (ref "S1") (pin "SW-") (pinfunction "SW-_SW-") (pintype "bidirectional"))
      (node (ref "S2") (pin "2") (pinfunction "2_2") (pintype "passive"))
      (node (ref "TP1") (pin "1") (pinfunction "1_1") (pintype "passive"))
      (node (ref "TP12") (pin "1") (pinfunction "1_1") (pintype "passive"))
      (node (ref "U1") (pin "21") (pinfunction "GND_21") (pintype "bidirectional"))
      (node (ref "U1") (pin "3") (pinfunction "GND_3") (pintype "bidirectional"))
      (node (ref "U1") (pin "5") (pinfunction "AGND_5") (pintype "bidirectional"))
      (node (ref "U2") (pin "2") (pinfunction "GND_2") (pintype "bidirectional"))
      (node (ref "U3") (pin "7") (pinfunction "GND_7") (pintype "power_in"))
      (node (ref "U4") (pin "1") (pinfunction "GND_1") (pintype "passive"))
      (node (ref "U4") (pin "2") (pinfunction "GND_2_2") (pintype "passive"))
      (node (ref "U5") (pin "3") (pinfunction "GND_3") (pintype "bidirectional"))
      (node (ref "U6") (pin "7") (pinfunction "GND_7") (pintype "power_in"))
      (node (ref "U7") (pin "10") (pinfunction "A1_10") (pintype "bidirectional"))
      (node (ref "U7") (pin "16") (pinfunction "GND_16") (pintype "bidirectional"))
      (node (ref "U7") (pin "7") (pinfunction "A2_7") (pintype "bidirectional"))
      (node (ref "U7") (pin "8") (pinfunction "~{G}_8") (pintype "bidirectional"))
      (node (ref "U7") (pin "9") (pinfunction "A0_9") (pintype "bidirectional"))
      (node (ref "U8") (pin "7") (pinfunction "GND_7") (pintype "bidirectional"))
      (node (ref "U8") (pin "PAD") (pinfunction "PAD_PAD") (pintype "bidirectional"))
      (node (ref "X1") (pin "2") (pinfunction "2_2") (pintype "passive"))
    )
    (net (code "42") (name "Net-(BZ1-+)") (class "Default")
      (node (ref "BZ1") (pin "1") (pinfunction "+_1") (pintype "passive"))
      (node (ref "C27") (pin "2") (pinfunction "2_2") (pintype "passive"))
      (node (ref "L7") (pin "2") (pinfunction "2_2") (pintype "passive"))
      (node (ref "R61") (pin "2") (pinfunction "2_2") (pintype "passive"))
    )
    (net (code "43") (name "Net-(BZ1--)") (class "Default")
      (node (ref "BZ1") (pin "2") (pinfunction "-_2") (pintype "passive"))
      (node (ref "Q9") (pin "3") (pinfunction "D_3") (pintype "passive"))
      (node (ref "R61") (pin "1") (pinfunction "1_1") (pintype "passive"))
    )
    (net (code "44") (name "Net-(C10-Pad2)") (class "Default")
      (node (ref "C10") (pin "2") (pinfunction "2_2") (pintype "passive"))
      (node (ref "R13") (pin "1") (pinfunction "1_1") (pintype "passive"))
      (node (ref "R65") (pin "2") (pinfunction "2_2") (pintype "passive"))
      (node (ref "S2") (pin "4") (pinfunction "4_4") (pintype "passive"))
    )
    (net (code "45") (name "Net-(C37-Pad1)") (class "Default")
      (node (ref "C37") (pin "1") (pinfunction "1_1") (pintype "passive"))
      (node (ref "R44") (pin "2") (pinfunction "2_2") (pintype "passive"))
    )
    (net (code "46") (name "Net-(D1-K)") (class "Default")
      (node (ref "C3") (pin "2") (pinfunction "2_2") (pintype "passive"))
      (node (ref "D1") (pin "-") (pinfunction "K_-") (pintype "bidirectional"))
      (node (ref "L1") (pin "1") (pinfunction "1_1") (pintype "passive"))
      (node (ref "U2") (pin "6") (pinfunction "LX_6") (pintype "bidirectional"))
    )
    (net (code "47") (name "Net-(D5-A)") (class "Default")
      (node (ref "D5") (pin "1") (pinfunction "A_1") (pintype "bidirectional"))
      (node (ref "PTC1") (pin "1") (pinfunction "1_1") (pintype "passive"))
    )
    (net (code "48") (name "Net-(D6-K)") (class "Default")
      (node (ref "C29") (pin "2") (pinfunction "2_2") (pintype "passive"))
      (node (ref "D6") (pin "2") (pinfunction "K_2") (pintype "bidirectional"))
      (node (ref "L2") (pin "1") (pinfunction "1_1") (pintype "passive"))
      (node (ref "U8") (pin "8") (pinfunction "PH_8") (pintype "bidirectional"))
    )
    (net (code "49") (name "Net-(IN+-1)") (class "Default")
      (node (ref "C36") (pin "2") (pinfunction "2_2") (pintype "passive"))
      (node (ref "IN+") (pin "P$1") (pinfunction "1_P$1") (pintype "bidirectional"))
      (node (ref "PTC1") (pin "2") (pinfunction "2_2") (pintype "passive"))
    )
    (net (code "50") (name "Net-(J6-DC)") (class "Default")
      (node (ref "J6") (pin "6") (pinfunction "DC_6") (pintype "bidirectional"))
      (node (ref "R24") (pin "2") (pinfunction "2_2") (pintype "passive"))
    )
    (net (code "51") (name "Net-(L3-Pad2)") (class "Default")
      (node (ref "L3") (pin "2") (pinfunction "2_2") (pintype "passive"))
      (node (ref "R26") (pin "1") (pinfunction "1_1") (pintype "passive"))
    )
    (net (code "52") (name "Net-(L4-Pad2)") (class "Default")
      (node (ref "L4") (pin "2") (pinfunction "2_2") (pintype "passive"))
      (node (ref "R22") (pin "1") (pinfunction "1_1") (pintype "passive"))
    )
    (net (code "53") (name "Net-(LED1-C)") (class "Default")
      (node (ref "LED1") (pin "K") (pinfunction "C_K") (pintype "passive"))
      (node (ref "Q2") (pin "3") (pinfunction "D_3") (pintype "passive"))
    )
    (net (code "54") (name "Net-(LED1-PadA)") (class "Default")
      (node (ref "LED1") (pin "A") (pinfunction "A_A") (pintype "passive"))
      (node (ref "R35") (pin "2") (pinfunction "2_2") (pintype "passive"))
    )
    (net (code "55") (name "Net-(LED2-C)") (class "Default")
      (node (ref "LED2") (pin "K") (pinfunction "C_K") (pintype "passive"))
      (node (ref "LED3") (pin "K") (pinfunction "C_K") (pintype "passive"))
      (node (ref "Q1") (pin "3") (pinfunction "D_3") (pintype "passive"))
    )
    (net (code "56") (name "Net-(LED2-PadA)") (class "Default")
      (node (ref "LED2") (pin "A") (pinfunction "A_A") (pintype "passive"))
      (node (ref "R38") (pin "2") (pinfunction "2_2") (pintype "passive"))
    )
    (net (code "57") (name "Net-(LED3-PadA)") (class "Default")
      (node (ref "LED3") (pin "A") (pinfunction "A_A") (pintype "passive"))
      (node (ref "R40") (pin "2") (pinfunction "2_2") (pintype "passive"))
    )
    (net (code "58") (name "Net-(OP1-C)") (class "Default")
      (node (ref "OP1") (pin "2") (pinfunction "C_2") (pintype "passive"))
      (node (ref "R26") (pin "2") (pinfunction "2_2") (pintype "passive"))
    )
    (net (code "59") (name "Net-(PEDAL+-1)") (class "Default")
      (node (ref "L3") (pin "1") (pinfunction "1_1") (pintype "passive"))
      (node (ref "PEDAL+") (pin "P$1") (pinfunction "1_P$1") (pintype "bidirectional"))
    )
    (net (code "60") (name "Net-(PEDAL--1)") (class "Default")
      (node (ref "L4") (pin "1") (pinfunction "1_1") (pintype "passive"))
      (node (ref "PEDAL-") (pin "P$1") (pinfunction "1_P$1") (pintype "bidirectional"))
    )
    (net (code "61") (name "Net-(Q2-G)") (class "Default")
      (node (ref "Q2") (pin "1") (pinfunction "G_1") (pintype "passive"))
      (node (ref "R31") (pin "2") (pinfunction "2_2") (pintype "passive"))
    )
    (net (code "62") (name "Net-(Q3-G)") (class "Default")
      (node (ref "Q3") (pin "1") (pinfunction "G_1") (pintype "passive"))
      (node (ref "R30") (pin "2") (pinfunction "2_2") (pintype "passive"))
    )
    (net (code "63") (name "Net-(Q4-D)") (class "Default")
      (node (ref "Q4") (pin "3") (pinfunction "D_3") (pintype "passive"))
      (node (ref "R41") (pin "1") (pinfunction "1_1") (pintype "passive"))
    )
    (net (code "64") (name "Net-(Q9-G)") (class "Default")
      (node (ref "Q9") (pin "1") (pinfunction "G_1") (pintype "passive"))
      (node (ref "R28") (pin "2") (pinfunction "2_2") (pintype "passive"))
      (node (ref "R32") (pin "1") (pinfunction "1_1") (pintype "passive"))
    )
    (net (code "65") (name "Net-(U1-PB1(OC1A))") (class "Default")
      (node (ref "R27") (pin "1") (pinfunction "1_1") (pintype "passive"))
      (node (ref "U1") (pin "13") (pinfunction "PB1(OC1A)_13") (pintype "bidirectional"))
    )
    (net (code "66") (name "Net-(U1-PB6(XTAL1{slash}TOSC1))") (class "Default")
      (node (ref "U1") (pin "7") (pinfunction "PB6(XTAL1/TOSC1)_7") (pintype "bidirectional"))
      (node (ref "X1") (pin "3") (pinfunction "3_3") (pintype "passive"))
    )
    (net (code "67") (name "Net-(U1-PB7(XTAL2{slash}TOSC2))") (class "Default")
      (node (ref "U1") (pin "8") (pinfunction "PB7(XTAL2/TOSC2)_8") (pintype "bidirectional"))
      (node (ref "X1") (pin "1") (pinfunction "1_1") (pintype "passive"))
    )
    (net (code "68") (name "Net-(U2-BST)") (class "Default")
      (node (ref "C3") (pin "1") (pinfunction "1_1") (pintype "passive"))
      (node (ref "U2") (pin "1") (pinfunction "BST_1") (pintype "bidirectional"))
    )
    (net (code "69") (name "Net-(U2-FB)") (class "Default")
      (node (ref "C5") (pin "1") (pinfunction "1_1") (pintype "passive"))
      (node (ref "R15") (pin "2") (pinfunction "2_2") (pintype "passive"))
      (node (ref "R16") (pin "1") (pinfunction "1_1") (pintype "passive"))
      (node (ref "U2") (pin "3") (pinfunction "FB_3") (pintype "bidirectional"))
    )
    (net (code "70") (name "Net-(U3A-I)") (class "Default")
      (node (ref "C49") (pin "2") (pinfunction "2_2") (pintype "passive"))
      (node (ref "R25") (pin "2") (pinfunction "2_2") (pintype "passive"))
      (node (ref "U3") (pin "13") (pinfunction "I_13") (pintype "input"))
    )
    (net (code "71") (name "Net-(U3B-O)") (class "Default")
      (node (ref "R2") (pin "1") (pinfunction "1_1") (pintype "passive"))
      (node (ref "U3") (pin "10") (pinfunction "O_10") (pintype "output"))
    )
    (net (code "72") (name "Net-(U3C-I)") (class "Default")
      (node (ref "C47") (pin "2") (pinfunction "2_2") (pintype "passive"))
      (node (ref "R2") (pin "2") (pinfunction "2_2") (pintype "passive"))
      (node (ref "U3") (pin "9") (pinfunction "I_9") (pintype "input"))
    )
    (net (code "73") (name "Net-(U3D-O)") (class "Default")
      (node (ref "R25") (pin "1") (pinfunction "1_1") (pintype "passive"))
      (node (ref "U3") (pin "2") (pinfunction "O_2") (pintype "output"))
    )
    (net (code "74") (name "Net-(U3E-I)") (class "Default")
      (node (ref "C48") (pin "2") (pinfunction "2_2") (pintype "passive"))
      (node (ref "R20") (pin "2") (pinfunction "2_2") (pintype "passive"))
      (node (ref "U3") (pin "3") (pinfunction "I_3") (pintype "input"))
    )
    (net (code "75") (name "Net-(U3F-O)") (class "Default")
      (node (ref "R20") (pin "1") (pinfunction "1_1") (pintype "passive"))
      (node (ref "U3") (pin "6") (pinfunction "O_6") (pintype "output"))
    )
    (net (code "76") (name "Net-(U4-RS-)") (class "Default")
      (node (ref "C43") (pin "2") (pinfunction "2_2") (pintype "passive"))
      (node (ref "R1") (pin "1") (pinfunction "1_1") (pintype "passive"))
      (node (ref "U4") (pin "4") (pinfunction "RS-_4") (pintype "input"))
    )
    (net (code "77") (name "Net-(U6A-O)") (class "Default")
      (node (ref "R39") (pin "1") (pinfunction "1_1") (pintype "passive"))
      (node (ref "U6") (pin "12") (pinfunction "O_12") (pintype "output"))
    )
    (net (code "78") (name "Net-(U6B-I)") (class "Default")
      (node (ref "C54") (pin "2") (pinfunction "2_2") (pintype "passive"))
      (node (ref "R39") (pin "2") (pinfunction "2_2") (pintype "passive"))
      (node (ref "U6") (pin "11") (pinfunction "I_11") (pintype "input"))
    )
    (net (code "79") (name "Net-(U6C-I)") (class "Default")
      (node (ref "C14") (pin "2") (pinfunction "2_2") (pintype "passive"))
      (node (ref "R33") (pin "2") (pinfunction "2_2") (pintype "passive"))
      (node (ref "U6") (pin "9") (pinfunction "I_9") (pintype "input"))
    )
    (net (code "80") (name "Net-(U6D-O)") (class "Default")
      (node (ref "R23") (pin "1") (pinfunction "1_1") (pintype "passive"))
      (node (ref "U6") (pin "2") (pinfunction "O_2") (pintype "output"))
    )
    (net (code "81") (name "Net-(U6E-I)") (class "Default")
      (node (ref "C11") (pin "2") (pinfunction "2_2") (pintype "passive"))
      (node (ref "R23") (pin "2") (pinfunction "2_2") (pintype "passive"))
      (node (ref "U6") (pin "3") (pinfunction "I_3") (pintype "input"))
    )
    (net (code "82") (name "Net-(U6F-O)") (class "Default")
      (node (ref "R33") (pin "1") (pinfunction "1_1") (pintype "passive"))
      (node (ref "U6") (pin "6") (pinfunction "O_6") (pintype "output"))
    )
    (net (code "83") (name "Net-(U7-DRAIN0)") (class "Default")
      (node (ref "R6") (pin "1") (pinfunction "1_1") (pintype "passive"))
      (node (ref "U7") (pin "3") (pinfunction "DRAIN0_3") (pintype "bidirectional"))
    )
    (net (code "84") (name "Net-(U7-DRAIN1)") (class "Default")
      (node (ref "R5") (pin "1") (pinfunction "1_1") (pintype "passive"))
      (node (ref "U7") (pin "4") (pinfunction "DRAIN1_4") (pintype "bidirectional"))
    )
    (net (code "85") (name "Net-(U7-DRAIN2)") (class "Default")
      (node (ref "R4") (pin "1") (pinfunction "1_1") (pintype "passive"))
      (node (ref "U7") (pin "5") (pinfunction "DRAIN2_5") (pintype "bidirectional"))
    )
    (net (code "86") (name "Net-(U7-DRAIN3)") (class "Default")
      (node (ref "R3") (pin "1") (pinfunction "1_1") (pintype "passive"))
      (node (ref "U7") (pin "6") (pinfunction "DRAIN3_6") (pintype "bidirectional"))
    )
    (net (code "87") (name "Net-(U7-DRAIN4)") (class "Default")
      (node (ref "R10") (pin "1") (pinfunction "1_1") (pintype "passive"))
      (node (ref "U7") (pin "11") (pinfunction "DRAIN4_11") (pintype "bidirectional"))
    )
    (net (code "88") (name "Net-(U7-DRAIN5)") (class "Default")
      (node (ref "R9") (pin "1") (pinfunction "1_1") (pintype "passive"))
      (node (ref "U7") (pin "12") (pinfunction "DRAIN5_12") (pintype "bidirectional"))
    )
    (net (code "89") (name "Net-(U7-DRAIN6)") (class "Default")
      (node (ref "R8") (pin "1") (pinfunction "1_1") (pintype "passive"))
      (node (ref "U7") (pin "13") (pinfunction "DRAIN6_13") (pintype "bidirectional"))
    )
    (net (code "90") (name "Net-(U7-DRAIN7)") (class "Default")
      (node (ref "R7") (pin "1") (pinfunction "1_1") (pintype "passive"))
      (node (ref "U7") (pin "14") (pinfunction "DRAIN7_14") (pintype "bidirectional"))
    )
    (net (code "91") (name "Net-(U7-SCL)") (class "Default")
      (node (ref "L5") (pin "1") (pinfunction "1_1") (pintype "passive"))
      (node (ref "U7") (pin "15") (pinfunction "SCL_15") (pintype "bidirectional"))
    )
    (net (code "92") (name "Net-(U7-SDA)") (class "Default")
      (node (ref "L6") (pin "1") (pinfunction "1_1") (pintype "passive"))
      (node (ref "U7") (pin "2") (pinfunction "SDA_2") (pintype "bidirectional"))
    )
    (net (code "93") (name "Net-(U8-BOOT)") (class "Default")
      (node (ref "C29") (pin "1") (pinfunction "1_1") (pintype "passive"))
      (node (ref "U8") (pin "1") (pinfunction "BOOT_1") (pintype "bidirectional"))
    )
    (net (code "94") (name "Net-(U8-COMP)") (class "Default")
      (node (ref "C37") (pin "2") (pinfunction "2_2") (pintype "passive"))
      (node (ref "C38") (pin "2") (pinfunction "2_2") (pintype "passive"))
      (node (ref "U8") (pin "6") (pinfunction "COMP_6") (pintype "bidirectional"))
    )
    (net (code "95") (name "Net-(U8-SS)") (class "Default")
      (node (ref "C30") (pin "2") (pinfunction "2_2") (pintype "passive"))
      (node (ref "U8") (pin "4") (pinfunction "SS_4") (pintype "bidirectional"))
    )
    (net (code "96") (name "Net-(U8-VSENSE)") (class "Default")
      (node (ref "C19") (pin "1") (pinfunction "1_1") (pintype "passive"))
      (node (ref "R10") (pin "2") (pinfunction "2_2") (pintype "passive"))
      (node (ref "R11") (pin "1") (pinfunction "1_1") (pintype "passive"))
      (node (ref "R3") (pin "2") (pinfunction "2_2") (pintype "passive"))
      (node (ref "R4") (pin "2") (pinfunction "2_2") (pintype "passive"))
      (node (ref "R5") (pin "2") (pinfunction "2_2") (pintype "passive"))
      (node (ref "R6") (pin "2") (pinfunction "2_2") (pintype "passive"))
      (node (ref "R7") (pin "2") (pinfunction "2_2") (pintype "passive"))
      (node (ref "R8") (pin "2") (pinfunction "2_2") (pintype "passive"))
      (node (ref "R9") (pin "2") (pinfunction "2_2") (pintype "passive"))
      (node (ref "U8") (pin "5") (pinfunction "VSENSE_5") (pintype "bidirectional"))
    )
    (net (code "97") (name "VCC") (class "Default")
      (node (ref "C17") (pin "1") (pinfunction "1_1") (pintype "passive"))
      (node (ref "C18") (pin "1") (pinfunction "1_1") (pintype "passive"))
      (node (ref "C21") (pin "1") (pinfunction "1_1") (pintype "passive"))
      (node (ref "C28") (pin "2") (pinfunction "2_2") (pintype "passive"))
      (node (ref "C35") (pin "1") (pinfunction "1_1") (pintype "passive"))
      (node (ref "C6") (pin "1") (pinfunction "1_1") (pintype "passive"))
      (node (ref "C7") (pin "2") (pinfunction "2_2") (pintype "passive"))
      (node (ref "D5") (pin "2") (pinfunction "K_2") (pintype "bidirectional"))
      (node (ref "L7") (pin "1") (pinfunction "1_1") (pintype "passive"))
      (node (ref "R41") (pin "2") (pinfunction "2_2") (pintype "passive"))
      (node (ref "R45") (pin "2") (pinfunction "2_2") (pintype "passive"))
      (node (ref "U2") (pin "5") (pinfunction "VCC_5") (pintype "bidirectional"))
      (node (ref "U5") (pin "2") (pinfunction "IN_2") (pintype "bidirectional"))
      (node (ref "U8") (pin "2") (pinfunction "VIN_2") (pintype "bidirectional"))
    )
    (net (code "98") (name "VCCIO") (class "Default")
      (node (ref "C16") (pin "2") (pinfunction "2_2") (pintype "passive"))
      (node (ref "C8") (pin "2") (pinfunction "2_2") (pintype "passive"))
      (node (ref "OP1") (pin "1") (pinfunction "A_1") (pintype "passive"))
      (node (ref "TP2") (pin "1") (pinfunction "1_1") (pintype "passive"))
      (node (ref "U5") (pin "1") (pinfunction "OUT_1") (pintype "bidirectional"))
    )
    (net (code "99") (name "unconnected-(D3-A-Pad1)") (class "Default")
      (node (ref "D3") (pin "1") (pinfunction "A_1") (pintype "passive"))
    )
    (net (code "100") (name "unconnected-(S2-Pad1)") (class "Default")
      (node (ref "S2") (pin "1") (pinfunction "1_1") (pintype "passive"))
    )
    (net (code "101") (name "unconnected-(S2-Pad3)") (class "Default")
      (node (ref "S2") (pin "3") (pinfunction "3_3") (pintype "passive"))
    )
  )
)
